# Battery_charger.net
KiCad netlist of a schematic drawn in Altium Designer
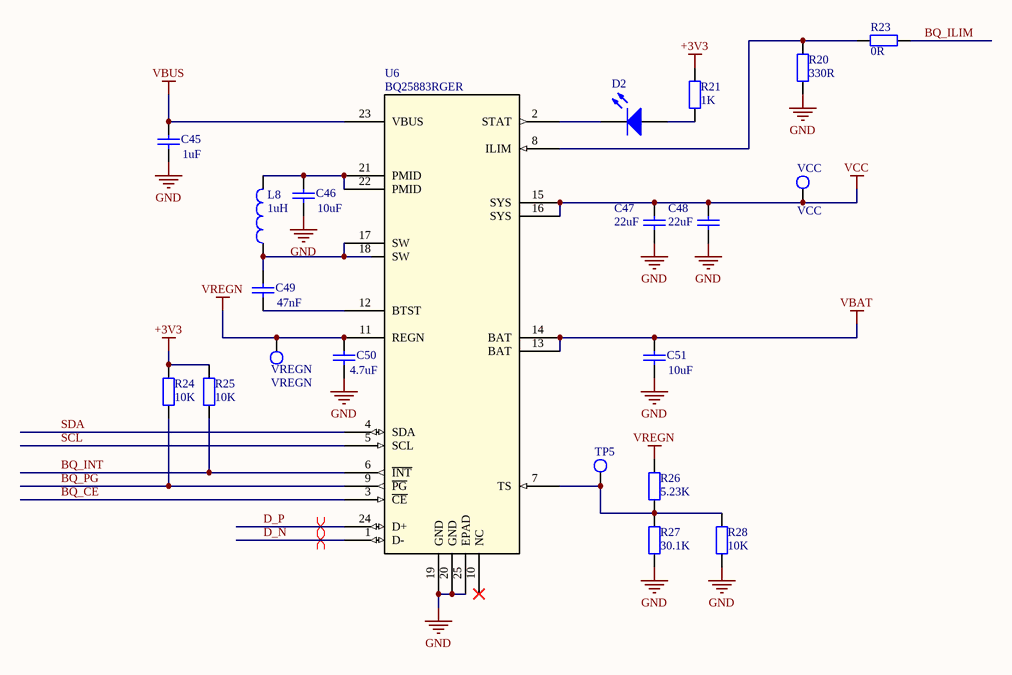
[diagram p0: Battery charger.SchDoc]

(export (version "E")
  (design (tool "Eeschema 10.0.6"))
  (components
    (comp (ref "C45")
      (value "1uF")
      (footprint "SMD-0402C")
      (description "Capacitor")
      (fields (field (name "PUBLISHER") "Altium Limited"))
      (libsource (lib "Miscellaneous Devices") (part "Cap"))
    )
    (comp (ref "C46")
      (value "10uF")
      (footprint "SMD-0805C")
      (description "Capacitor")
      (fields (field (name "PUBLISHER") "Altium Limited"))
      (libsource (lib "Miscellaneous Devices") (part "Cap"))
    )
    (comp (ref "C47")
      (value "22uF")
      (footprint "SMD-0805C")
      (description "Capacitor")
      (fields (field (name "PUBLISHER") "Altium Limited"))
      (libsource (lib "Miscellaneous Devices") (part "Cap"))
    )
    (comp (ref "C48")
      (value "22uF")
      (footprint "SMD-0805C")
      (description "Capacitor")
      (fields (field (name "PUBLISHER") "Altium Limited"))
      (libsource (lib "Miscellaneous Devices") (part "Cap"))
    )
    (comp (ref "C49")
      (value "47nF")
      (footprint "SMD-0402C")
      (description "Capacitor")
      (fields (field (name "PUBLISHER") "Altium Limited"))
      (libsource (lib "Miscellaneous Devices") (part "Cap"))
    )
    (comp (ref "C50")
      (value "4.7uF")
      (footprint "SMD-0603C")
      (description "Capacitor")
      (fields (field (name "PUBLISHER") "Altium Limited"))
      (libsource (lib "Miscellaneous Devices") (part "Cap"))
    )
    (comp (ref "C51")
      (value "10uF")
      (footprint "SMD-0805C")
      (description "Capacitor")
      (fields (field (name "PUBLISHER") "Altium Limited"))
      (libsource (lib "Miscellaneous Devices") (part "Cap"))
    )
    (comp (ref "D2")
      (value "~")
      (footprint "LED 0603")
      (description "Single Colour LEDs SMD Green 2.5-16 mcd")
      (fields (field (name "PUBLISHER") "Altium Limited"))
      (libsource (lib "Miscellaneous Devices") (part "LED1"))
    )
    (comp (ref "L8")
      (value "1uH")
      (footprint "SMD-0806_L")
      (description "Inductor")
      (fields (field (name "PUBLISHER") "Altium Limited"))
      (libsource (lib "Miscellaneous Devices") (part "Inductor"))
    )
    (comp (ref "R20")
      (value "330R")
      (footprint "SMD-0402-RES")
      (description "Resistor")
      (fields (field (name "PUBLISHER") "Altium Limited"))
      (libsource (lib "Miscellaneous Devices") (part "Res2"))
    )
    (comp (ref "R21")
      (value "1K")
      (footprint "SMD-0402-RES")
      (description "Resistor")
      (fields (field (name "PUBLISHER") "Altium Limited"))
      (libsource (lib "") (part "Res2_1"))
    )
    (comp (ref "R23")
      (value "0R")
      (footprint "SMD-0402-RES")
      (description "Resistor")
      (fields (field (name "PUBLISHER") "Altium Limited"))
      (libsource (lib "") (part "Res2_2"))
    )
    (comp (ref "R24")
      (value "10K")
      (footprint "SMD-0402-RES")
      (description "Resistor")
      (fields (field (name "PUBLISHER") "Altium Limited"))
      (libsource (lib "Miscellaneous Devices") (part "Res2"))
    )
    (comp (ref "R25")
      (value "10K")
      (footprint "SMD-0402-RES")
      (description "Resistor")
      (fields (field (name "PUBLISHER") "Altium Limited"))
      (libsource (lib "Miscellaneous Devices") (part "Res2"))
    )
    (comp (ref "R26")
      (value "5.23K")
      (footprint "SMD-0402-RES")
      (description "Resistor")
      (fields (field (name "PUBLISHER") "Altium Limited"))
      (libsource (lib "Miscellaneous Devices") (part "Res2"))
    )
    (comp (ref "R27")
      (value "30.1K")
      (footprint "SMD-0402-RES")
      (description "Resistor")
      (fields (field (name "PUBLISHER") "Altium Limited"))
      (libsource (lib "Miscellaneous Devices") (part "Res2"))
    )
    (comp (ref "R28")
      (value "10K")
      (footprint "SMD-0402-RES")
      (description "Resistor")
      (fields (field (name "PUBLISHER") "Altium Limited"))
      (libsource (lib "Miscellaneous Devices") (part "Res2"))
    )
    (comp (ref "TP5")
      (value "VREGN")
      (footprint "testpoint 1 mm")
      (libsource (lib "Schematic_library") (part "testpoint"))
    )
    (comp (ref "U6")
      (value "BQ25883RGER")
      (footprint "BQ25883RGER")
      (fields (field (name "COPYRIGHT") "Copyright (C) 2025 Ultra Librarian. All rights reserved."))
      (libsource (lib "Schematic_library") (part "BQ25883RGER"))
    )
    (comp (ref "VCC")
      (value "VCC")
      (footprint "testpoint 1 mm")
      (libsource (lib "Schematic_library") (part "testpoint"))
    )
    (comp (ref "VREGN")
      (value "VREGN")
      (footprint "testpoint 1 mm")
      (libsource (lib "Schematic_library") (part "testpoint"))
    )
  )
  (nets
    (net (code "1") (name "+3V3") (class "Default")
      (node (ref "R21") (pin "1") (pinfunction "1_1") (pintype "passive"))
      (node (ref "R24") (pin "2") (pinfunction "2_2") (pintype "passive"))
      (node (ref "R25") (pin "2") (pinfunction "2_2") (pintype "passive"))
    )
    (net (code "2") (name "/BQ_CE") (class "Default")
      (node (ref "U6") (pin "3") (pinfunction "~{CE}_3") (pintype "input"))
    )
    (net (code "3") (name "/BQ_ILIM") (class "Default")
      (node (ref "R23") (pin "1") (pinfunction "1_1") (pintype "passive"))
    )
    (net (code "4") (name "/BQ_INT") (class "Default")
      (node (ref "R25") (pin "1") (pinfunction "1_1") (pintype "passive"))
      (node (ref "U6") (pin "6") (pinfunction "~{INT}_6") (pintype "output"))
    )
    (net (code "5") (name "/BQ_PG") (class "Default")
      (node (ref "R24") (pin "1") (pinfunction "1_1") (pintype "passive"))
      (node (ref "U6") (pin "9") (pinfunction "~{PG}_9") (pintype "output"))
    )
    (net (code "6") (name "/D_N") (class "Default")
      (node (ref "U6") (pin "1") (pinfunction "D-_1") (pintype "bidirectional"))
    )
    (net (code "7") (name "/D_P") (class "Default")
      (node (ref "U6") (pin "24") (pinfunction "D+_24") (pintype "bidirectional"))
    )
    (net (code "8") (name "/SCL") (class "Default")
      (node (ref "U6") (pin "5") (pinfunction "SCL_5") (pintype "input"))
    )
    (net (code "9") (name "/SDA") (class "Default")
      (node (ref "U6") (pin "4") (pinfunction "SDA_4") (pintype "bidirectional"))
    )
    (net (code "10") (name "GND") (class "Default")
      (node (ref "C45") (pin "1") (pinfunction "1_1") (pintype "passive"))
      (node (ref "C46") (pin "1") (pinfunction "1_1") (pintype "passive"))
      (node (ref "C47") (pin "1") (pinfunction "1_1") (pintype "passive"))
      (node (ref "C48") (pin "1") (pinfunction "1_1") (pintype "passive"))
      (node (ref "C50") (pin "1") (pinfunction "1_1") (pintype "passive"))
      (node (ref "C51") (pin "1") (pinfunction "1_1") (pintype "passive"))
      (node (ref "R20") (pin "1") (pinfunction "1_1") (pintype "passive"))
      (node (ref "R27") (pin "1") (pinfunction "1_1") (pintype "passive"))
      (node (ref "R28") (pin "1") (pinfunction "1_1") (pintype "passive"))
      (node (ref "U6") (pin "19") (pinfunction "GND_19") (pintype "power_in"))
      (node (ref "U6") (pin "20") (pinfunction "GND_20") (pintype "power_in"))
      (node (ref "U6") (pin "25") (pinfunction "EPAD_25") (pintype "power_in"))
    )
    (net (code "11") (name "Net-(C46-Pad2)") (class "Default")
      (node (ref "C46") (pin "2") (pinfunction "2_2") (pintype "passive"))
      (node (ref "L8") (pin "2") (pinfunction "2_2") (pintype "passive"))
      (node (ref "U6") (pin "21") (pinfunction "PMID_21") (pintype "power_in"))
      (node (ref "U6") (pin "22") (pinfunction "PMID_22") (pintype "power_in"))
    )
    (net (code "12") (name "Net-(C49-Pad2)") (class "Default")
      (node (ref "C49") (pin "2") (pinfunction "2_2") (pintype "passive"))
      (node (ref "L8") (pin "1") (pinfunction "1_1") (pintype "passive"))
      (node (ref "U6") (pin "17") (pinfunction "SW_17") (pintype "power_in"))
      (node (ref "U6") (pin "18") (pinfunction "SW_18") (pintype "power_in"))
    )
    (net (code "13") (name "Net-(D2-A)") (class "Default")
      (node (ref "D2") (pin "1") (pinfunction "A_1") (pintype "passive"))
      (node (ref "R21") (pin "2") (pinfunction "2_2") (pintype "passive"))
    )
    (net (code "14") (name "Net-(D2-K)") (class "Default")
      (node (ref "D2") (pin "2") (pinfunction "K_2") (pintype "passive"))
      (node (ref "U6") (pin "2") (pinfunction "STAT_2") (pintype "output"))
    )
    (net (code "15") (name "Net-(U6-BTST)") (class "Default")
      (node (ref "C49") (pin "1") (pinfunction "1_1") (pintype "passive"))
      (node (ref "U6") (pin "12") (pinfunction "BTST_12") (pintype "power_in"))
    )
    (net (code "16") (name "Net-(U6-ILIM)") (class "Default")
      (node (ref "R20") (pin "2") (pinfunction "2_2") (pintype "passive"))
      (node (ref "R23") (pin "2") (pinfunction "2_2") (pintype "passive"))
      (node (ref "U6") (pin "8") (pinfunction "ILIM_8") (pintype "input"))
    )
    (net (code "17") (name "Net-(U6-TS)") (class "Default")
      (node (ref "R26") (pin "1") (pinfunction "1_1") (pintype "passive"))
      (node (ref "R27") (pin "2") (pinfunction "2_2") (pintype "passive"))
      (node (ref "R28") (pin "2") (pinfunction "2_2") (pintype "passive"))
      (node (ref "TP5") (pin "1") (pinfunction "1_1") (pintype "passive"))
      (node (ref "U6") (pin "7") (pinfunction "TS_7") (pintype "input"))
    )
    (net (code "18") (name "VBAT") (class "Default")
      (node (ref "C51") (pin "2") (pinfunction "2_2") (pintype "passive"))
      (node (ref "U6") (pin "13") (pinfunction "BAT_13") (pintype "power_in"))
      (node (ref "U6") (pin "14") (pinfunction "BAT_14") (pintype "power_in"))
    )
    (net (code "19") (name "VBUS") (class "Default")
      (node (ref "C45") (pin "2") (pinfunction "2_2") (pintype "passive"))
      (node (ref "U6") (pin "23") (pinfunction "VBUS_23") (pintype "power_in"))
    )
    (net (code "20") (name "VCC") (class "Default")
      (node (ref "C47") (pin "2") (pinfunction "2_2") (pintype "passive"))
      (node (ref "C48") (pin "2") (pinfunction "2_2") (pintype "passive"))
      (node (ref "U6") (pin "15") (pinfunction "SYS_15") (pintype "power_in"))
      (node (ref "U6") (pin "16") (pinfunction "SYS_16") (pintype "power_in"))
      (node (ref "VCC") (pin "1") (pinfunction "1_1") (pintype "passive"))
    )
    (net (code "21") (name "VREGN") (class "Default")
      (node (ref "C50") (pin "2") (pinfunction "2_2") (pintype "passive"))
      (node (ref "R26") (pin "2") (pinfunction "2_2") (pintype "passive"))
      (node (ref "U6") (pin "11") (pinfunction "REGN_11") (pintype "power_in"))
      (node (ref "VREGN") (pin "1") (pinfunction "1_1") (pintype "passive"))
    )
    (net (code "22") (name "unconnected-(U6-NC-Pad10)") (class "Default")
      (node (ref "U6") (pin "10") (pinfunction "NC_10") (pintype "passive+no_connect"))
    )
  )
)
